# Liv_Flo_Sign_MCU_V1_0.net
KiCad netlist of a schematic drawn in Altium Designer
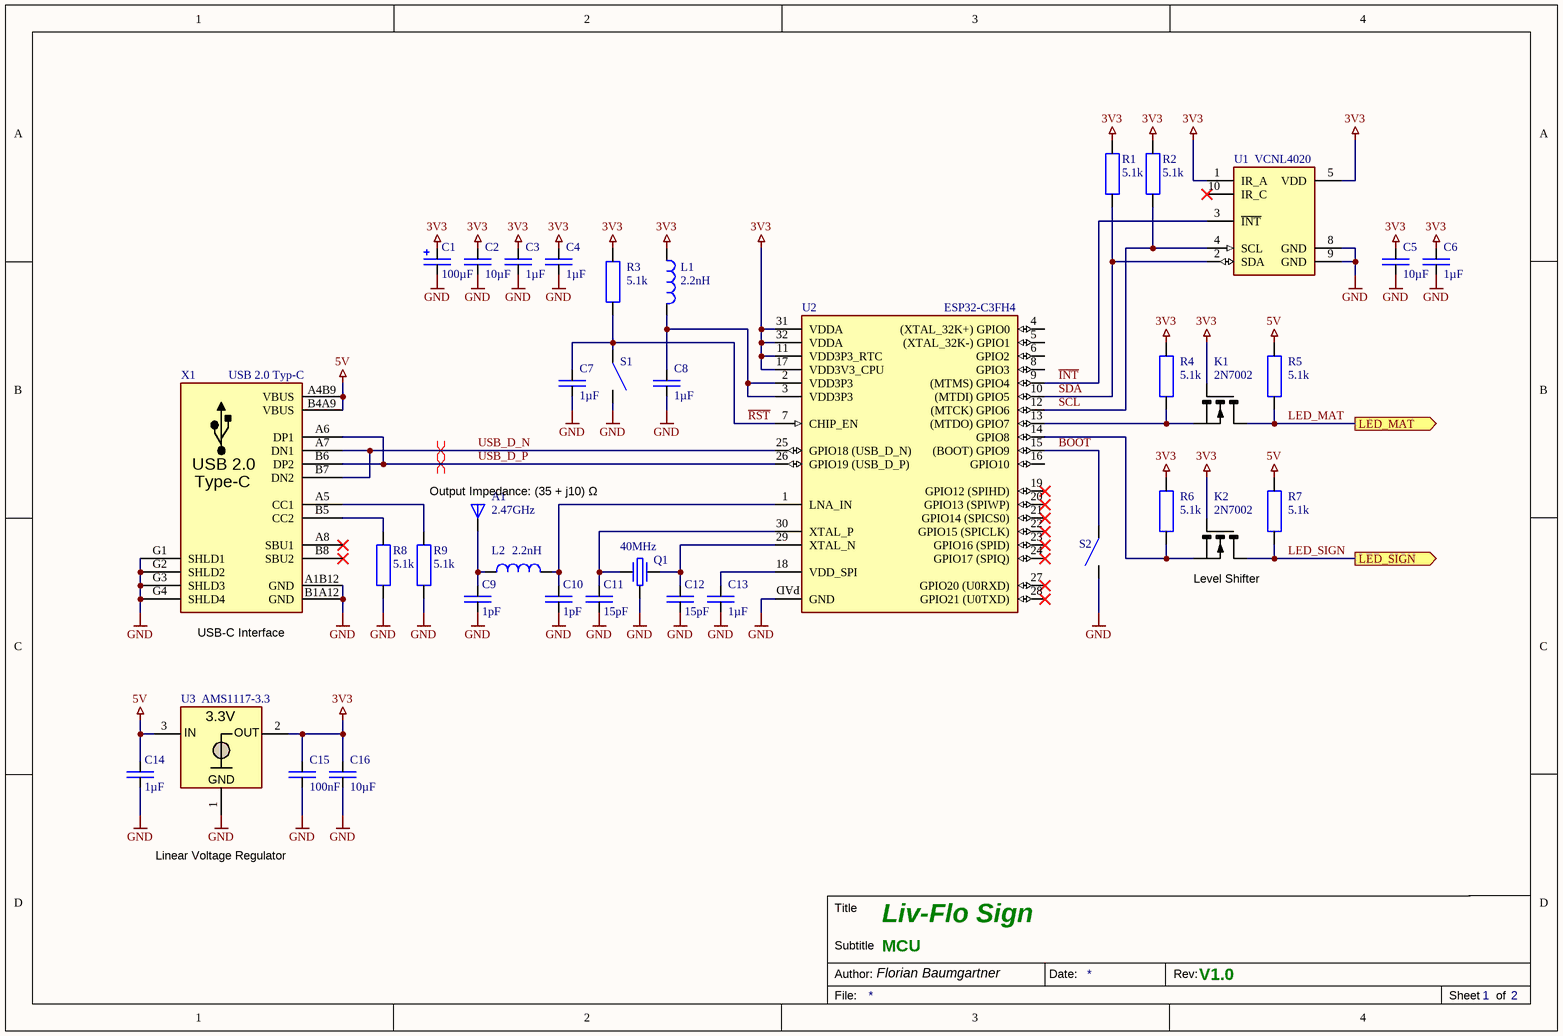
[diagram p0: Liv_Flo_Sign_MCU_V1.0.SchDoc]

(export (version "E")
  (design (tool "Eeschema 10.0.6"))
  (components
    (comp (ref "A1")
      (value "2.47GHz")
      (footprint "SMD Chip-Antenna 7020 (SLDA72-2R470G-S1TF)")
      (description "Chip-Antenna")
      (libsource (lib "WallLightRemote") (part "A-Chip-Antenna"))
    )
    (comp (ref "C1")
      (value "100µF")
      (footprint "SMD Tantalkondensator 1210 +")
      (description "CAP-Elko")
      (libsource (lib "TFS Integrated Library") (part "C-ELCAP"))
    )
    (comp (ref "C2")
      (value "10µF")
      (footprint "SMD Keramikkondensator 0603")
      (description "SMD Ceramic Capacitor E6")
      (libsource (lib "Ceramic Capacitors-E6") (part "E6 - 10uF"))
    )
    (comp (ref "C3")
      (value "1µF")
      (footprint "SMD Keramikkondensator 0603")
      (description "CAP-MK")
      (libsource (lib "AudioAmp") (part "C-CAPACITOR"))
    )
    (comp (ref "C4")
      (value "1µF")
      (footprint "SMD Keramikkondensator 0603")
      (description "CAP-MK")
      (libsource (lib "AudioAmp") (part "C-CAPACITOR"))
    )
    (comp (ref "C5")
      (value "10µF")
      (footprint "SMD Keramikkondensator 0603")
      (description "SMD Ceramic Capacitor E6")
      (libsource (lib "Ceramic Capacitors-E6") (part "E6 - 10uF"))
    )
    (comp (ref "C6")
      (value "1µF")
      (footprint "SMD Keramikkondensator 0603")
      (description "CAP-MK")
      (libsource (lib "AudioAmp") (part "C-CAPACITOR"))
    )
    (comp (ref "C7")
      (value "1µF")
      (footprint "SMD Keramikkondensator 0603")
      (description "CAP-MK")
      (libsource (lib "AudioAmp") (part "C-CAPACITOR"))
    )
    (comp (ref "C8")
      (value "1µF")
      (footprint "SMD Keramikkondensator 0603")
      (description "CAP-MK")
      (libsource (lib "AudioAmp") (part "C-CAPACITOR"))
    )
    (comp (ref "C9")
      (value "1pF")
      (footprint "SMD Keramikkondensator 0402")
      (description "CAP-MK")
      (libsource (lib "AudioAmp") (part "C-CAPACITOR"))
    )
    (comp (ref "C10")
      (value "1pF")
      (footprint "SMD Keramikkondensator 0402")
      (description "CAP-MK")
      (libsource (lib "AudioAmp") (part "C-CAPACITOR"))
    )
    (comp (ref "C11")
      (value "15pF")
      (footprint "SMD Keramikkondensator 0603")
      (description "CAP-MK")
      (libsource (lib "AudioAmp") (part "C-CAPACITOR"))
    )
    (comp (ref "C12")
      (value "15pF")
      (footprint "SMD Keramikkondensator 0603")
      (description "CAP-MK")
      (libsource (lib "AudioAmp") (part "C-CAPACITOR"))
    )
    (comp (ref "C13")
      (value "1µF")
      (footprint "SMD Keramikkondensator 0603")
      (description "CAP-MK")
      (libsource (lib "AudioAmp") (part "C-CAPACITOR"))
    )
    (comp (ref "C14")
      (value "1µF")
      (footprint "SMD Keramikkondensator 0603")
      (description "SMD Ceramic Capacitor E6")
      (libsource (lib "Fleet-Monitor") (part "E6 - 1uF"))
    )
    (comp (ref "C15")
      (value "100nF")
      (footprint "SMD Keramikkondensator 0603")
      (description "SMD Ceramic Capacitor E6")
      (libsource (lib "Ceramic Capacitors-E6") (part "E6 - 100nF"))
    )
    (comp (ref "C16")
      (value "10µF")
      (footprint "SMD Keramikkondensator 0603")
      (description "SMD Ceramic Capacitor E6")
      (libsource (lib "Ceramic Capacitors-E6") (part "E6 - 10uF"))
    )
    (comp (ref "K1")
      (value "2N7002")
      (footprint "SMD MOSFET SOT-23")
      (description "MOSFET N-Channel")
      (libsource (lib "Nixie-Test") (part "K-FET{colon}NIGE"))
    )
    (comp (ref "K2")
      (value "2N7002")
      (footprint "SMD MOSFET SOT-23")
      (description "MOSFET N-Channel")
      (libsource (lib "Nixie-Test") (part "K-FET{colon}NIGE"))
    )
    (comp (ref "L1")
      (value "2.2nH")
      (footprint "SMD Inductor 0402")
      (description "Chip Inductor")
      (libsource (lib "TFS Integrated Library") (part "R-COIL (HF)"))
    )
    (comp (ref "L2")
      (value "2.2nH")
      (footprint "SMD Inductor 0402")
      (description "Chip Inductor")
      (libsource (lib "TFS Integrated Library") (part "R-COIL (HF)"))
    )
    (comp (ref "Q1")
      (value "40MHz")
      (footprint "SMD Crystal 2.5X2.0X0.5")
      (libsource (lib "WallLightRemote") (part "B-QUARZ-CAP"))
    )
    (comp (ref "R1")
      (value "5.1k")
      (footprint "SMD Widerstand 0603")
      (description "RES (E=Heizwiderstand B=Messwandler)")
      (libsource (lib "TFS Integrated Library") (part "R-RESISTOR"))
    )
    (comp (ref "R2")
      (value "5.1k")
      (footprint "SMD Widerstand 0603")
      (description "RES (E=Heizwiderstand B=Messwandler)")
      (libsource (lib "TFS Integrated Library") (part "R-RESISTOR"))
    )
    (comp (ref "R3")
      (value "5.1k")
      (footprint "SMD Widerstand 0603")
      (description "RES (E=Heizwiderstand B=Messwandler)")
      (libsource (lib "TFS Integrated Library") (part "R-RESISTOR"))
    )
    (comp (ref "R4")
      (value "5.1k")
      (footprint "SMD Widerstand 0603")
      (description "RES (E=Heizwiderstand B=Messwandler)")
      (libsource (lib "TFS Integrated Library") (part "R-RESISTOR"))
    )
    (comp (ref "R5")
      (value "5.1k")
      (footprint "SMD Widerstand 0603")
      (description "RES (E=Heizwiderstand B=Messwandler)")
      (libsource (lib "TFS Integrated Library") (part "R-RESISTOR"))
    )
    (comp (ref "R6")
      (value "5.1k")
      (footprint "SMD Widerstand 0603")
      (description "RES (E=Heizwiderstand B=Messwandler)")
      (libsource (lib "TFS Integrated Library") (part "R-RESISTOR"))
    )
    (comp (ref "R7")
      (value "5.1k")
      (footprint "SMD Widerstand 0603")
      (description "RES (E=Heizwiderstand B=Messwandler)")
      (libsource (lib "TFS Integrated Library") (part "R-RESISTOR"))
    )
    (comp (ref "R8")
      (value "5.1k")
      (footprint "SMD Widerstand 0603")
      (description "RES (E=Heizwiderstand B=Messwandler)")
      (libsource (lib "TFS Integrated Library") (part "R-RESISTOR"))
    )
    (comp (ref "R9")
      (value "5.1k")
      (footprint "SMD Widerstand 0603")
      (description "RES (E=Heizwiderstand B=Messwandler)")
      (libsource (lib "TFS Integrated Library") (part "R-RESISTOR"))
    )
    (comp (ref "S1")
      (value "SMD-Button")
      (footprint "SMD Button 4.2x3.2x2.5")
      (description "Button SPST")
      (libsource (lib "Switches") (part "Button 3mmx2.5mm"))
    )
    (comp (ref "S2")
      (value "SMD-Button")
      (footprint "SMD Button 4.2x3.2x2.5")
      (description "Button SPST")
      (libsource (lib "Switches") (part "Button 3mmx2.5mm"))
    )
    (comp (ref "U1")
      (value "VCNL4020")
      (footprint "SMD Proximity Sensor (VCNL4020)")
      (description "Proximity and Ambient Light Sensor")
      (libsource (lib "Liv_Flo_Sign") (part "U-VCNL4020-GS08"))
    )
    (comp (ref "U2")
      (value "ESP32-C3FH4")
      (footprint "SMD IC QFN-32")
      (description "2.4 GHz Wi­Fi + Bluetooth® LE SoC")
      (libsource (lib "Liv_Flo_Sign") (part "U-ESP32-C3FH4"))
    )
    (comp (ref "U3")
      (value "AMS1117-3.3")
      (footprint "SMD IC SOT-223")
      (description "LDO Voltage Regulator")
      (libsource (lib "NintendoSwitchBridge_Prototype") (part "U-AMS1117-3.3"))
    )
    (comp (ref "X1")
      (value "USB 2.0 Typ-C")
      (footprint "SMD USB-C Socket (A40-00119)")
      (description "Typ-C")
      (libsource (lib "Custom ST-Link") (part "X-USB-Buchse"))
    )
  )
  (nets
    (net (code "1") (name "/BOOT") (class "Default")
      (node (ref "S2") (pin "1") (pinfunction "1_1") (pintype "passive"))
      (node (ref "U2") (pin "15") (pinfunction "(BOOT)_GPIO9_15") (pintype "bidirectional"))
    )
    (net (code "2") (name "/LED_MAT") (class "Default")
      (node (ref "K1") (pin "D") (pinfunction "D_D") (pintype "passive"))
      (node (ref "R5") (pin "2") (pinfunction "2_2") (pintype "passive"))
    )
    (net (code "3") (name "/LED_SIGN") (class "Default")
      (node (ref "K2") (pin "D") (pinfunction "D_D") (pintype "passive"))
      (node (ref "R7") (pin "2") (pinfunction "2_2") (pintype "passive"))
    )
    (net (code "4") (name "/SCL") (class "Default")
      (node (ref "R2") (pin "2") (pinfunction "2_2") (pintype "passive"))
      (node (ref "U1") (pin "4") (pinfunction "SCL_4") (pintype "input"))
      (node (ref "U2") (pin "12") (pinfunction "(MTCK)_GPIO6_12") (pintype "bidirectional"))
    )
    (net (code "5") (name "/SDA") (class "Default")
      (node (ref "R1") (pin "2") (pinfunction "2_2") (pintype "passive"))
      (node (ref "U1") (pin "2") (pinfunction "SDA_2") (pintype "bidirectional"))
      (node (ref "U2") (pin "10") (pinfunction "(MTDI)_GPIO5_10") (pintype "bidirectional"))
    )
    (net (code "6") (name "/USB_D_N") (class "Default")
      (node (ref "U2") (pin "25") (pinfunction "GPIO18_(USB_D_N)_25") (pintype "bidirectional"))
      (node (ref "X1") (pin "A7") (pinfunction "DN1_A7") (pintype "passive"))
      (node (ref "X1") (pin "B7") (pinfunction "DN2_B7") (pintype "passive"))
    )
    (net (code "7") (name "/USB_D_P") (class "Default")
      (node (ref "U2") (pin "26") (pinfunction "GPIO19_(USB_D_P)_26") (pintype "bidirectional"))
      (node (ref "X1") (pin "A6") (pinfunction "DP1_A6") (pintype "passive"))
      (node (ref "X1") (pin "B6") (pinfunction "DP2_B6") (pintype "passive"))
    )
    (net (code "8") (name "/~{INT}") (class "Default")
      (node (ref "U1") (pin "3") (pinfunction "~{INT}_3") (pintype "open_collector"))
      (node (ref "U2") (pin "9") (pinfunction "(MTMS)_GPIO4_9") (pintype "bidirectional"))
    )
    (net (code "9") (name "/~{RST}") (class "Default")
      (node (ref "C7") (pin "2") (pinfunction "2_2") (pintype "passive"))
      (node (ref "R3") (pin "2") (pinfunction "2_2") (pintype "passive"))
      (node (ref "S1") (pin "1") (pinfunction "1_1") (pintype "passive"))
      (node (ref "U2") (pin "7") (pinfunction "CHIP_EN_7") (pintype "input"))
    )
    (net (code "10") (name "3V3") (class "Default")
      (node (ref "C1") (pin "P") (pinfunction "+_P") (pintype "passive"))
      (node (ref "C15") (pin "2") (pinfunction "2_2") (pintype "passive"))
      (node (ref "C16") (pin "2") (pinfunction "2_2") (pintype "passive"))
      (node (ref "C2") (pin "2") (pinfunction "2_2") (pintype "passive"))
      (node (ref "C3") (pin "2") (pinfunction "2_2") (pintype "passive"))
      (node (ref "C4") (pin "2") (pinfunction "2_2") (pintype "passive"))
      (node (ref "C5") (pin "2") (pinfunction "2_2") (pintype "passive"))
      (node (ref "C6") (pin "2") (pinfunction "2_2") (pintype "passive"))
      (node (ref "K1") (pin "G") (pinfunction "G_G") (pintype "passive"))
      (node (ref "K2") (pin "G") (pinfunction "G_G") (pintype "passive"))
      (node (ref "L1") (pin "1") (pinfunction "1_1") (pintype "passive"))
      (node (ref "R1") (pin "1") (pinfunction "1_1") (pintype "passive"))
      (node (ref "R2") (pin "1") (pinfunction "1_1") (pintype "passive"))
      (node (ref "R3") (pin "1") (pinfunction "1_1") (pintype "passive"))
      (node (ref "R4") (pin "1") (pinfunction "1_1") (pintype "passive"))
      (node (ref "R6") (pin "1") (pinfunction "1_1") (pintype "passive"))
      (node (ref "U1") (pin "1") (pinfunction "IR_A_1") (pintype "passive"))
      (node (ref "U1") (pin "5") (pinfunction "VDD_5") (pintype "power_in"))
      (node (ref "U2") (pin "11") (pinfunction "VDD3P3_RTC_11") (pintype "power_in"))
      (node (ref "U2") (pin "17") (pinfunction "VDD3V3_CPU_17") (pintype "power_in"))
      (node (ref "U2") (pin "31") (pinfunction "VDDA_31") (pintype "power_in"))
      (node (ref "U2") (pin "32") (pinfunction "VDDA_32") (pintype "power_in"))
      (node (ref "U3") (pin "2") (pinfunction "OUT_2") (pintype "power_in"))
    )
    (net (code "11") (name "5V") (class "Default")
      (node (ref "C14") (pin "2") (pinfunction "2_2") (pintype "passive"))
      (node (ref "R5") (pin "1") (pinfunction "1_1") (pintype "passive"))
      (node (ref "R7") (pin "1") (pinfunction "1_1") (pintype "passive"))
      (node (ref "U3") (pin "3") (pinfunction "IN_3") (pintype "power_in"))
      (node (ref "X1") (pin "A4B9") (pinfunction "VBUS_A4B9") (pintype "passive"))
      (node (ref "X1") (pin "B4A9") (pinfunction "VBUS_B4A9") (pintype "passive"))
    )
    (net (code "12") (name "GND") (class "Default")
      (node (ref "C1") (pin "M") (pinfunction "-_M") (pintype "passive"))
      (node (ref "C10") (pin "2") (pinfunction "2_2") (pintype "passive"))
      (node (ref "C11") (pin "2") (pinfunction "2_2") (pintype "passive"))
      (node (ref "C12") (pin "2") (pinfunction "2_2") (pintype "passive"))
      (node (ref "C13") (pin "1") (pinfunction "1_1") (pintype "passive"))
      (node (ref "C14") (pin "1") (pinfunction "1_1") (pintype "passive"))
      (node (ref "C15") (pin "1") (pinfunction "1_1") (pintype "passive"))
      (node (ref "C16") (pin "1") (pinfunction "1_1") (pintype "passive"))
      (node (ref "C2") (pin "1") (pinfunction "1_1") (pintype "passive"))
      (node (ref "C3") (pin "1") (pinfunction "1_1") (pintype "passive"))
      (node (ref "C4") (pin "1") (pinfunction "1_1") (pintype "passive"))
      (node (ref "C5") (pin "1") (pinfunction "1_1") (pintype "passive"))
      (node (ref "C6") (pin "1") (pinfunction "1_1") (pintype "passive"))
      (node (ref "C7") (pin "1") (pinfunction "1_1") (pintype "passive"))
      (node (ref "C8") (pin "1") (pinfunction "1_1") (pintype "passive"))
      (node (ref "C9") (pin "2") (pinfunction "2_2") (pintype "passive"))
      (node (ref "Q1") (pin "3") (pinfunction "3_3") (pintype "passive"))
      (node (ref "R8") (pin "2") (pinfunction "2_2") (pintype "passive"))
      (node (ref "R9") (pin "2") (pinfunction "2_2") (pintype "passive"))
      (node (ref "S1") (pin "2") (pinfunction "2_2") (pintype "passive"))
      (node (ref "S2") (pin "2") (pinfunction "2_2") (pintype "passive"))
      (node (ref "U1") (pin "8") (pinfunction "GND_8") (pintype "power_in"))
      (node (ref "U1") (pin "9") (pinfunction "GND_9") (pintype "power_in"))
      (node (ref "U2") (pin "PAD") (pinfunction "GND_PAD") (pintype "power_in"))
      (node (ref "U3") (pin "1") (pinfunction "GND_1") (pintype "power_in"))
      (node (ref "X1") (pin "A1B12") (pinfunction "GND_A1B12") (pintype "passive"))
      (node (ref "X1") (pin "B1A12") (pinfunction "GND_B1A12") (pintype "passive"))
      (node (ref "X1") (pin "G1") (pinfunction "SHLD1_G1") (pintype "passive"))
      (node (ref "X1") (pin "G2") (pinfunction "SHLD2_G2") (pintype "passive"))
      (node (ref "X1") (pin "G3") (pinfunction "SHLD3_G3") (pintype "passive"))
      (node (ref "X1") (pin "G4") (pinfunction "SHLD4_G4") (pintype "passive"))
    )
    (net (code "13") (name "Net-(A1-Pad1)") (class "Default")
      (node (ref "A1") (pin "1") (pinfunction "1_1") (pintype "passive"))
      (node (ref "C9") (pin "1") (pinfunction "1_1") (pintype "passive"))
      (node (ref "L2") (pin "1") (pinfunction "1_1") (pintype "passive"))
    )
    (net (code "14") (name "Net-(C8-Pad2)") (class "Default")
      (node (ref "C8") (pin "2") (pinfunction "2_2") (pintype "passive"))
      (node (ref "L1") (pin "2") (pinfunction "2_2") (pintype "passive"))
      (node (ref "U2") (pin "2") (pinfunction "VDD3P3_2") (pintype "power_in"))
      (node (ref "U2") (pin "3") (pinfunction "VDD3P3_3") (pintype "power_in"))
    )
    (net (code "15") (name "Net-(U2-(MTDO)_GPIO7)") (class "Default")
      (node (ref "K1") (pin "S") (pinfunction "S_S") (pintype "passive"))
      (node (ref "R4") (pin "2") (pinfunction "2_2") (pintype "passive"))
      (node (ref "U2") (pin "13") (pinfunction "(MTDO)_GPIO7_13") (pintype "bidirectional"))
    )
    (net (code "16") (name "Net-(U2-GPIO8)") (class "Default")
      (node (ref "K2") (pin "S") (pinfunction "S_S") (pintype "passive"))
      (node (ref "R6") (pin "2") (pinfunction "2_2") (pintype "passive"))
      (node (ref "U2") (pin "14") (pinfunction "GPIO8_14") (pintype "bidirectional"))
    )
    (net (code "17") (name "Net-(U2-LNA_IN)") (class "Default")
      (node (ref "C10") (pin "1") (pinfunction "1_1") (pintype "passive"))
      (node (ref "L2") (pin "2") (pinfunction "2_2") (pintype "passive"))
      (node (ref "U2") (pin "1") (pinfunction "LNA_IN_1") (pintype "passive"))
    )
    (net (code "18") (name "Net-(U2-VDD_SPI)") (class "Default")
      (node (ref "C13") (pin "2") (pinfunction "2_2") (pintype "passive"))
      (node (ref "U2") (pin "18") (pinfunction "VDD_SPI_18") (pintype "power_in"))
    )
    (net (code "19") (name "Net-(U2-XTAL_N)") (class "Default")
      (node (ref "C12") (pin "1") (pinfunction "1_1") (pintype "passive"))
      (node (ref "Q1") (pin "2") (pinfunction "2_2") (pintype "passive"))
      (node (ref "U2") (pin "29") (pinfunction "XTAL_N_29") (pintype "passive"))
    )
    (net (code "20") (name "Net-(U2-XTAL_P)") (class "Default")
      (node (ref "C11") (pin "1") (pinfunction "1_1") (pintype "passive"))
      (node (ref "Q1") (pin "1") (pinfunction "1_1") (pintype "passive"))
      (node (ref "U2") (pin "30") (pinfunction "XTAL_P_30") (pintype "passive"))
    )
    (net (code "21") (name "Net-(X1-CC1)") (class "Default")
      (node (ref "R9") (pin "1") (pinfunction "1_1") (pintype "passive"))
      (node (ref "X1") (pin "A5") (pinfunction "CC1_A5") (pintype "passive"))
    )
    (net (code "22") (name "Net-(X1-CC2)") (class "Default")
      (node (ref "R8") (pin "1") (pinfunction "1_1") (pintype "passive"))
      (node (ref "X1") (pin "B5") (pinfunction "CC2_B5") (pintype "passive"))
    )
    (net (code "23") (name "unconnected-(U1-IR_C-Pad10)") (class "Default")
      (node (ref "U1") (pin "10") (pinfunction "IR_C_10") (pintype "passive+no_connect"))
    )
    (net (code "24") (name "unconnected-(U1-NC-Pad6)") (class "Default")
      (node (ref "U1") (pin "6") (pinfunction "NC_6") (pintype "passive"))
    )
    (net (code "25") (name "unconnected-(U1-NC-Pad7)") (class "Default")
      (node (ref "U1") (pin "7") (pinfunction "NC_7") (pintype "passive"))
    )
    (net (code "26") (name "unconnected-(U2-(XTAL_32K+)_GPIO0-Pad4)") (class "Default")
      (node (ref "U2") (pin "4") (pinfunction "(XTAL_32K+)_GPIO0_4") (pintype "bidirectional"))
    )
    (net (code "27") (name "unconnected-(U2-(XTAL_32K-)_GPIO1-Pad5)") (class "Default")
      (node (ref "U2") (pin "5") (pinfunction "(XTAL_32K-)_GPIO1_5") (pintype "bidirectional"))
    )
    (net (code "28") (name "unconnected-(U2-GPIO2-Pad6)") (class "Default")
      (node (ref "U2") (pin "6") (pinfunction "GPIO2_6") (pintype "bidirectional"))
    )
    (net (code "29") (name "unconnected-(U2-GPIO3-Pad8)") (class "Default")
      (node (ref "U2") (pin "8") (pinfunction "GPIO3_8") (pintype "bidirectional"))
    )
    (net (code "30") (name "unconnected-(U2-GPIO10-Pad16)") (class "Default")
      (node (ref "U2") (pin "16") (pinfunction "GPIO10_16") (pintype "bidirectional"))
    )
    (net (code "31") (name "unconnected-(U2-GPIO12_(SPIHD)-Pad19)") (class "Default")
      (node (ref "U2") (pin "19") (pinfunction "GPIO12_(SPIHD)_19") (pintype "bidirectional+no_connect"))
    )
    (net (code "32") (name "unconnected-(U2-GPIO13_(SPIWP)-Pad20)") (class "Default")
      (node (ref "U2") (pin "20") (pinfunction "GPIO13_(SPIWP)_20") (pintype "bidirectional+no_connect"))
    )
    (net (code "33") (name "unconnected-(U2-GPIO14_(SPICS0)-Pad21)") (class "Default")
      (node (ref "U2") (pin "21") (pinfunction "GPIO14_(SPICS0)_21") (pintype "bidirectional+no_connect"))
    )
    (net (code "34") (name "unconnected-(U2-GPIO15_(SPICLK)-Pad22)") (class "Default")
      (node (ref "U2") (pin "22") (pinfunction "GPIO15_(SPICLK)_22") (pintype "bidirectional+no_connect"))
    )
    (net (code "35") (name "unconnected-(U2-GPIO16_(SPID)-Pad23)") (class "Default")
      (node (ref "U2") (pin "23") (pinfunction "GPIO16_(SPID)_23") (pintype "bidirectional+no_connect"))
    )
    (net (code "36") (name "unconnected-(U2-GPIO17_(SPIQ)-Pad24)") (class "Default")
      (node (ref "U2") (pin "24") (pinfunction "GPIO17_(SPIQ)_24") (pintype "bidirectional+no_connect"))
    )
    (net (code "37") (name "unconnected-(U2-GPIO20_(U0RXD)-Pad27)") (class "Default")
      (node (ref "U2") (pin "27") (pinfunction "GPIO20_(U0RXD)_27") (pintype "bidirectional+no_connect"))
    )
    (net (code "38") (name "unconnected-(U2-GPIO21_(U0TXD)-Pad28)") (class "Default")
      (node (ref "U2") (pin "28") (pinfunction "GPIO21_(U0TXD)_28") (pintype "bidirectional+no_connect"))
    )
    (net (code "39") (name "unconnected-(X1-SBU1-PadA8)") (class "Default")
      (node (ref "X1") (pin "A8") (pinfunction "SBU1_A8") (pintype "passive+no_connect"))
    )
    (net (code "40") (name "unconnected-(X1-SBU2-PadB8)") (class "Default")
      (node (ref "X1") (pin "B8") (pinfunction "SBU2_B8") (pintype "passive+no_connect"))
    )
  )
)
